# batteryBalancer.net
KiCad netlist of a schematic drawn in EAGLE
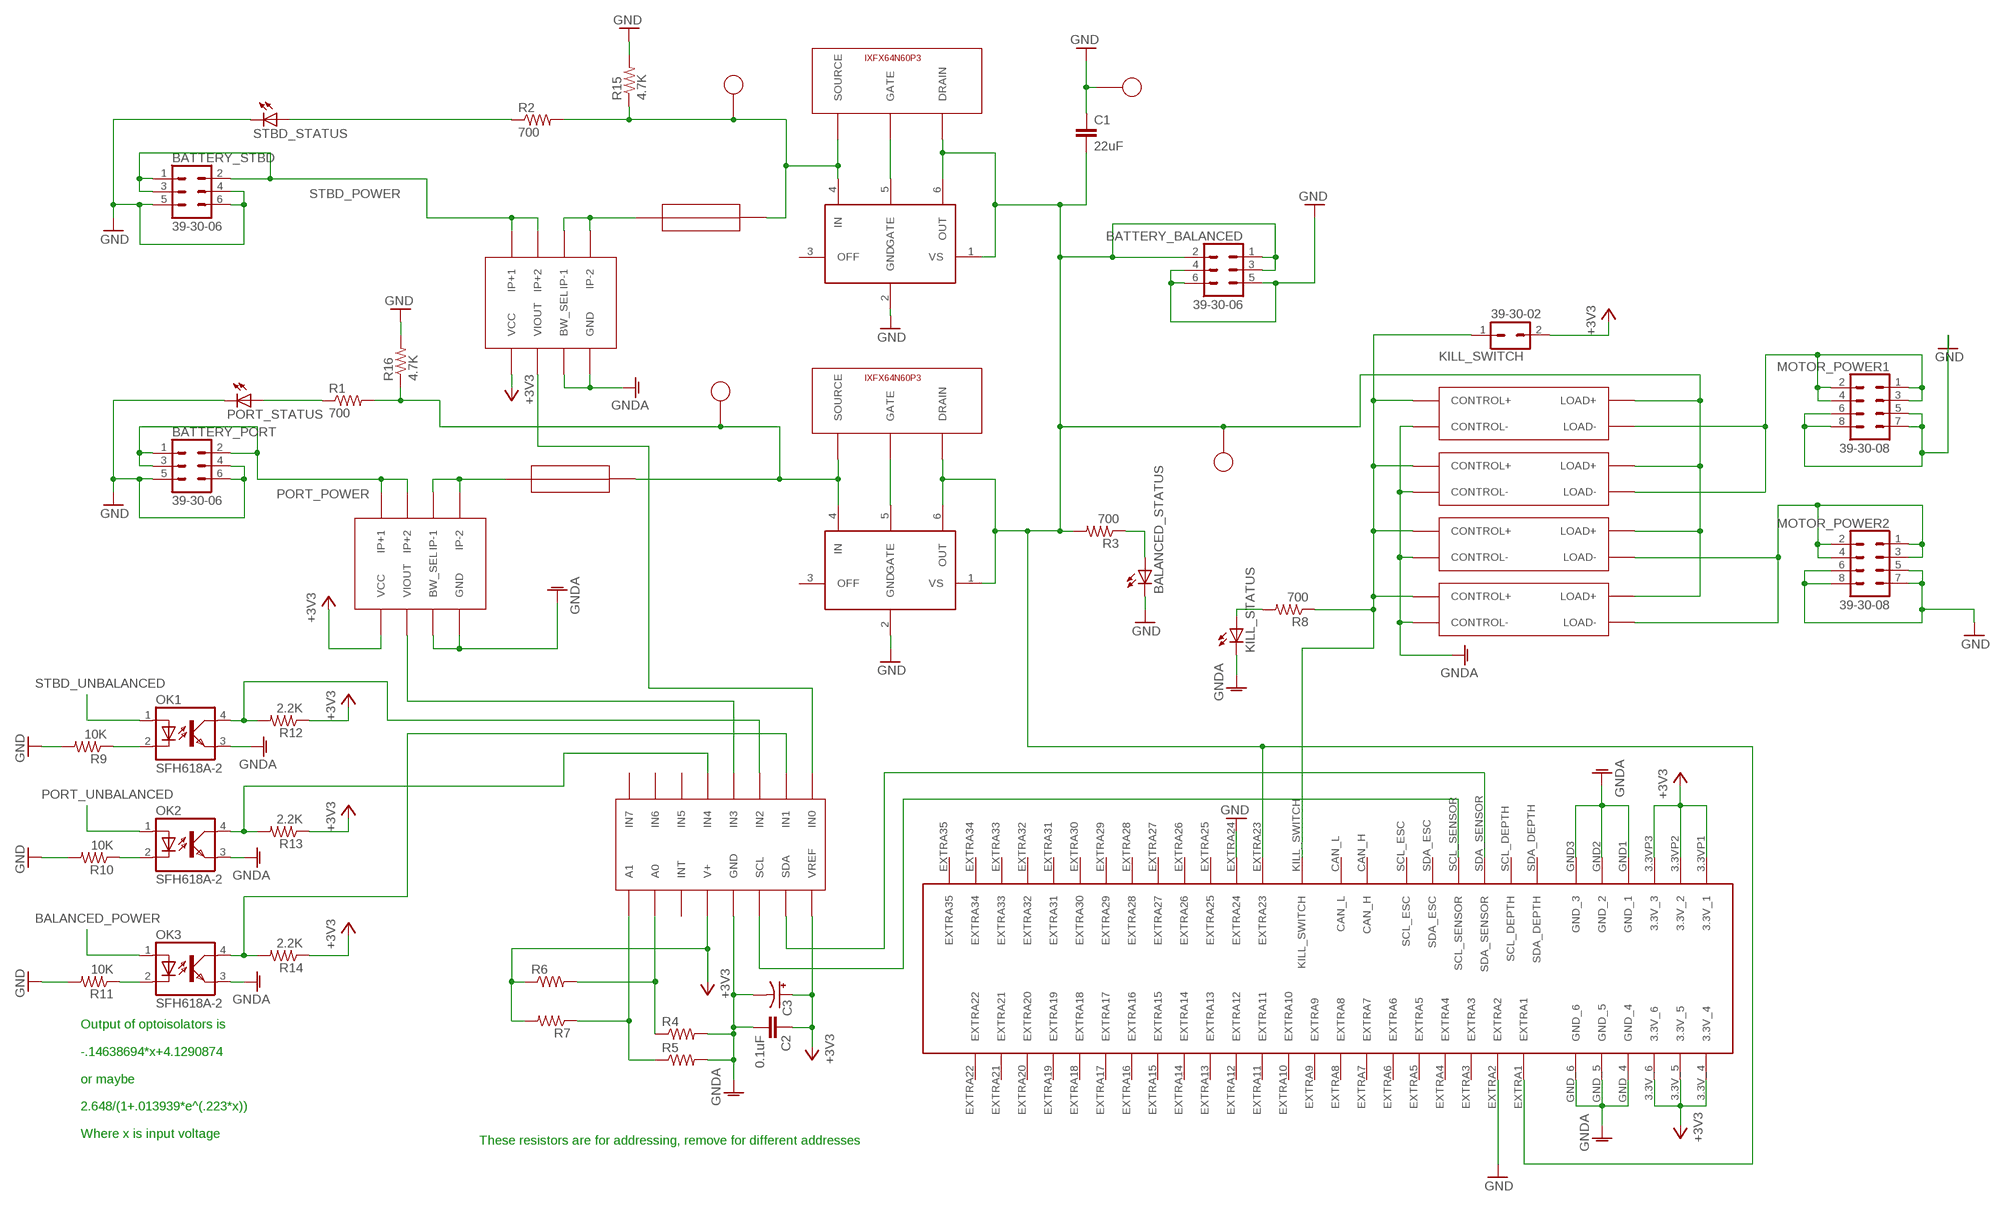
[diagram p0: schematic, sheet 1]

(export (version "E")
  (design (tool "Eeschema 10.0.6"))
  (components
    (comp (ref "ADC")
      (value "ADC128D818")
      (footprint "eagle-import:TSSOP-16")
      (libsource (lib "eagle-import") (part "ADC128D818"))
    )
    (comp (ref "BALANCED_STATUS")
      (value "LTST-S270GKT")
      (footprint "eagle-import:LTST-S270GKT")
      (libsource (lib "eagle-import") (part "LTST-S270GKT"))
    )
    (comp (ref "BATTERY_BALANCED")
      (value "39-30-06")
      (footprint "eagle-import:39-30-_06_")
      (libsource (lib "eagle-import") (part "39-30-?06?"))
    )
    (comp (ref "BATTERY_PORT")
      (value "39-30-06")
      (footprint "eagle-import:39-30-_06_")
      (libsource (lib "eagle-import") (part "39-30-?06?"))
    )
    (comp (ref "BATTERY_STBD")
      (value "39-30-06")
      (footprint "eagle-import:39-30-_06_")
      (libsource (lib "eagle-import") (part "39-30-?06?"))
    )
    (comp (ref "C1")
      (value "22uF")
      (footprint "eagle-import:CAP-PTH-SMALL-KIT")
      (libsource (lib "eagle-import") (part "0.1UF-KIT-EZ-50V-20%"))
    )
    (comp (ref "C2")
      (value "0.1uF")
      (footprint "eagle-import:CAP-PTH-SMALL-KIT")
      (libsource (lib "eagle-import") (part "0.1UF-KIT-EZ-50V-20%"))
    )
    (comp (ref "C3")
      (value "CPOL-USE2-4")
      (footprint "eagle-import:E2-4")
      (libsource (lib "eagle-import") (part "CPOL-USE2-4"))
    )
    (comp (ref "EDGE_CONNECTOR")
      (value "5530843")
      (footprint "eagle-import:5530843-6-BOARDFINGERS")
      (libsource (lib "eagle-import") (part "5530843"))
    )
    (comp (ref "KILL_STATUS")
      (value "LTST-S270GKT")
      (footprint "eagle-import:LTST-S270GKT")
      (libsource (lib "eagle-import") (part "LTST-S270GKT"))
    )
    (comp (ref "KILL_SWITCH")
      (value "39-30-02")
      (footprint "eagle-import:39-30-_02_")
      (libsource (lib "eagle-import") (part "39-30-?02?"))
    )
    (comp (ref "MOTOR_POWER1")
      (value "39-30-08")
      (footprint "eagle-import:39-30-_08_")
      (libsource (lib "eagle-import") (part "39-30-?08?"))
    )
    (comp (ref "MOTOR_POWER2")
      (value "39-30-08")
      (footprint "eagle-import:39-30-_08_")
      (libsource (lib "eagle-import") (part "39-30-?08?"))
    )
    (comp (ref "OK1")
      (value "SFH618A-2")
      (footprint "eagle-import:DIP4")
      (fields (field (name "MF") "VISHAY/TELEFUNKEN"))
      (libsource (lib "eagle-import") (part "SFH618?A-2"))
    )
    (comp (ref "OK2")
      (value "SFH618A-2")
      (footprint "eagle-import:DIP4")
      (fields (field (name "MF") "VISHAY/TELEFUNKEN"))
      (libsource (lib "eagle-import") (part "SFH618?A-2"))
    )
    (comp (ref "OK3")
      (value "SFH618A-2")
      (footprint "eagle-import:DIP4")
      (fields (field (name "MF") "VISHAY/TELEFUNKEN"))
      (libsource (lib "eagle-import") (part "SFH618?A-2"))
    )
    (comp (ref "PORT_CS")
      (value "ACS722")
      (footprint "eagle-import:SOIC-8")
      (libsource (lib "eagle-import") (part "ACS722"))
    )
    (comp (ref "PORT_FC")
      (value "LM5050-1")
      (footprint "eagle-import:SOT23-6")
      (libsource (lib "eagle-import") (part "LM5050-1"))
    )
    (comp (ref "PORT_FET")
      (value "IXFX64N60P3")
      (footprint "eagle-import:IXFX64N60P3")
      (libsource (lib "eagle-import") (part "IXFX64N60P3"))
    )
    (comp (ref "PORT_FUSE")
      (value "01220083Z")
      (footprint "eagle-import:01220083Z")
      (libsource (lib "eagle-import") (part "01220083Z"))
    )
    (comp (ref "PORT_STATUS")
      (value "LTST-S270GKT")
      (footprint "eagle-import:LTST-S270GKT")
      (libsource (lib "eagle-import") (part "LTST-S270GKT"))
    )
    (comp (ref "R1")
      (value "700")
      (footprint "eagle-import:0207_7")
      (libsource (lib "eagle-import") (part "R-US_0207/7"))
    )
    (comp (ref "R2")
      (value "700")
      (footprint "eagle-import:0207_7")
      (libsource (lib "eagle-import") (part "R-US_0207/7"))
    )
    (comp (ref "R3")
      (value "700")
      (footprint "eagle-import:0207_7")
      (libsource (lib "eagle-import") (part "R-US_0207/7"))
    )
    (comp (ref "R4")
      (value "R-US_0204/5")
      (footprint "eagle-import:0204_5")
      (libsource (lib "eagle-import") (part "resistor_348_R-US_0204/5"))
    )
    (comp (ref "R5")
      (value "R-US_0204/5")
      (footprint "eagle-import:0204_5")
      (libsource (lib "eagle-import") (part "resistor_348_R-US_0204/5"))
    )
    (comp (ref "R6")
      (value "R-US_0204/5")
      (footprint "eagle-import:0204_5")
      (libsource (lib "eagle-import") (part "resistor_348_R-US_0204/5"))
    )
    (comp (ref "R7")
      (value "R-US_0204/5")
      (footprint "eagle-import:0204_5")
      (libsource (lib "eagle-import") (part "resistor_348_R-US_0204/5"))
    )
    (comp (ref "R8")
      (value "700")
      (footprint "eagle-import:0207_7")
      (libsource (lib "eagle-import") (part "R-US_0207/7"))
    )
    (comp (ref "R9")
      (value "10K")
      (footprint "eagle-import:0207_7")
      (libsource (lib "eagle-import") (part "R-US_0207/7"))
    )
    (comp (ref "R10")
      (value "10K")
      (footprint "eagle-import:0207_7")
      (libsource (lib "eagle-import") (part "R-US_0207/7"))
    )
    (comp (ref "R11")
      (value "10K")
      (footprint "eagle-import:0207_7")
      (libsource (lib "eagle-import") (part "R-US_0207/7"))
    )
    (comp (ref "R12")
      (value "2.2K")
      (footprint "eagle-import:0207_7")
      (libsource (lib "eagle-import") (part "R-US_0207/7"))
    )
    (comp (ref "R13")
      (value "2.2K")
      (footprint "eagle-import:0207_7")
      (libsource (lib "eagle-import") (part "R-US_0207/7"))
    )
    (comp (ref "R14")
      (value "2.2K")
      (footprint "eagle-import:0207_7")
      (libsource (lib "eagle-import") (part "R-US_0207/7"))
    )
    (comp (ref "R15")
      (value "4.7K")
      (footprint "eagle-import:0207_7")
      (libsource (lib "eagle-import") (part "R-US_0207/7"))
    )
    (comp (ref "R16")
      (value "4.7K")
      (footprint "eagle-import:0207_7")
      (libsource (lib "eagle-import") (part "R-US_0207/7"))
    )
    (comp (ref "RELAY2")
      (value "CMX60D20")
      (footprint "eagle-import:CMX60D20")
      (libsource (lib "eagle-import") (part "CMX60D20"))
    )
    (comp (ref "RELAY3")
      (value "CMX60D20")
      (footprint "eagle-import:CMX60D20")
      (libsource (lib "eagle-import") (part "CMX60D20"))
    )
    (comp (ref "RELAY4")
      (value "CMX60D20")
      (footprint "eagle-import:CMX60D20")
      (libsource (lib "eagle-import") (part "CMX60D20"))
    )
    (comp (ref "RLAY1")
      (value "CMX60D20")
      (footprint "eagle-import:CMX60D20")
      (libsource (lib "eagle-import") (part "CMX60D20"))
    )
    (comp (ref "STBD_CS")
      (value "ACS722")
      (footprint "eagle-import:SOIC-8")
      (libsource (lib "eagle-import") (part "ACS722"))
    )
    (comp (ref "STBD_FC")
      (value "LM5050-1")
      (footprint "eagle-import:SOT23-6")
      (libsource (lib "eagle-import") (part "LM5050-1"))
    )
    (comp (ref "STBD_FET")
      (value "IXFX64N60P3")
      (footprint "eagle-import:IXFX64N60P3")
      (libsource (lib "eagle-import") (part "IXFX64N60P3"))
    )
    (comp (ref "STBD_FUSE")
      (value "01220083Z")
      (footprint "eagle-import:01220083Z")
      (libsource (lib "eagle-import") (part "01220083Z"))
    )
    (comp (ref "STBD_STATUS")
      (value "LTST-S270GKT")
      (footprint "eagle-import:LTST-S270GKT")
      (libsource (lib "eagle-import") (part "LTST-S270GKT"))
    )
    (comp (ref "U$1")
      (value "5010_C")
      (footprint "eagle-import:5010_C")
      (libsource (lib "eagle-import") (part "5010_C"))
    )
    (comp (ref "U$2")
      (value "5010_C")
      (footprint "eagle-import:5010_C")
      (libsource (lib "eagle-import") (part "5010_C"))
    )
    (comp (ref "U$3")
      (value "5010_C")
      (footprint "eagle-import:5010_C")
      (libsource (lib "eagle-import") (part "5010_C"))
    )
    (comp (ref "U$4")
      (value "5010_C")
      (footprint "eagle-import:5010_C")
      (libsource (lib "eagle-import") (part "5010_C"))
    )
  )
  (nets
    (net (code "1") (name "+3V3") (class "Default")
      (node (ref "ADC") (pin "V+") (pinfunction "V+_V+") (pintype "bidirectional"))
      (node (ref "ADC") (pin "VREF") (pinfunction "VREF_VREF") (pintype "bidirectional"))
      (node (ref "C2") (pin "1") (pinfunction "1_1") (pintype "passive"))
      (node (ref "C3") (pin "+") (pinfunction "+_+") (pintype "passive"))
      (node (ref "EDGE_CONNECTOR") (pin "3.3VP1") (pinfunction "3.3V_1_3.3VP1") (pintype "bidirectional"))
      (node (ref "EDGE_CONNECTOR") (pin "3.3VP2") (pinfunction "3.3V_2_3.3VP2") (pintype "bidirectional"))
      (node (ref "EDGE_CONNECTOR") (pin "3.3VP3") (pinfunction "3.3V_3_3.3VP3") (pintype "bidirectional"))
      (node (ref "EDGE_CONNECTOR") (pin "3.3V_4") (pinfunction "3.3V_4_3.3V_4") (pintype "bidirectional"))
      (node (ref "EDGE_CONNECTOR") (pin "3.3V_5") (pinfunction "3.3V_5_3.3V_5") (pintype "bidirectional"))
      (node (ref "EDGE_CONNECTOR") (pin "3.3V_6") (pinfunction "3.3V_6_3.3V_6") (pintype "bidirectional"))
      (node (ref "KILL_SWITCH") (pin "2") (pinfunction "2_2") (pintype "passive"))
      (node (ref "PORT_CS") (pin "VCC") (pinfunction "VCC_VCC") (pintype "bidirectional"))
      (node (ref "R12") (pin "1") (pinfunction "1_1") (pintype "passive"))
      (node (ref "R13") (pin "1") (pinfunction "1_1") (pintype "passive"))
      (node (ref "R14") (pin "1") (pinfunction "1_1") (pintype "passive"))
      (node (ref "R6") (pin "1") (pinfunction "1_1") (pintype "passive"))
      (node (ref "R7") (pin "2") (pinfunction "2_2") (pintype "passive"))
      (node (ref "STBD_CS") (pin "VCC") (pinfunction "VCC_VCC") (pintype "bidirectional"))
    )
    (net (code "2") (name "/BALANCED_POWER") (class "Default")
      (node (ref "BATTERY_BALANCED") (pin "1") (pinfunction "1_1") (pintype "passive"))
      (node (ref "BATTERY_BALANCED") (pin "2") (pinfunction "2_2") (pintype "passive"))
      (node (ref "BATTERY_BALANCED") (pin "3") (pinfunction "3_3") (pintype "passive"))
      (node (ref "C1") (pin "2") (pinfunction "2_2") (pintype "passive"))
      (node (ref "EDGE_CONNECTOR") (pin "EXTRA1") (pinfunction "EXTRA1_EXTRA1") (pintype "bidirectional"))
      (node (ref "EDGE_CONNECTOR") (pin "EXTRA23") (pinfunction "EXTRA23_EXTRA23") (pintype "bidirectional"))
      (node (ref "OK3") (pin "1") (pinfunction "A_1") (pintype "passive"))
      (node (ref "PORT_FC") (pin "1") (pinfunction "VS_1") (pintype "bidirectional"))
      (node (ref "PORT_FC") (pin "6") (pinfunction "OUT_6") (pintype "bidirectional"))
      (node (ref "PORT_FET") (pin "DRAIN") (pinfunction "DRAIN_DRAIN") (pintype "bidirectional"))
      (node (ref "R3") (pin "2") (pinfunction "2_2") (pintype "passive"))
      (node (ref "RELAY2") (pin "LOAD+") (pinfunction "LOAD+_LOAD+") (pintype "bidirectional"))
      (node (ref "RELAY3") (pin "LOAD+") (pinfunction "LOAD+_LOAD+") (pintype "bidirectional"))
      (node (ref "RELAY4") (pin "LOAD+") (pinfunction "LOAD+_LOAD+") (pintype "bidirectional"))
      (node (ref "RLAY1") (pin "LOAD+") (pinfunction "LOAD+_LOAD+") (pintype "bidirectional"))
      (node (ref "STBD_FC") (pin "1") (pinfunction "VS_1") (pintype "bidirectional"))
      (node (ref "STBD_FC") (pin "6") (pinfunction "OUT_6") (pintype "bidirectional"))
      (node (ref "STBD_FET") (pin "DRAIN") (pinfunction "DRAIN_DRAIN") (pintype "bidirectional"))
      (node (ref "U$3") (pin "P$1") (pinfunction "P$1_P$1") (pintype "bidirectional"))
    )
    (net (code "3") (name "/PORT_POWER") (class "Default")
      (node (ref "BATTERY_PORT") (pin "1") (pinfunction "1_1") (pintype "passive"))
      (node (ref "BATTERY_PORT") (pin "2") (pinfunction "2_2") (pintype "passive"))
      (node (ref "BATTERY_PORT") (pin "3") (pinfunction "3_3") (pintype "passive"))
      (node (ref "PORT_CS") (pin "IP+1") (pinfunction "IP+1_IP+1") (pintype "bidirectional"))
      (node (ref "PORT_CS") (pin "IP+2") (pinfunction "IP+2_IP+2") (pintype "bidirectional"))
    )
    (net (code "4") (name "/PORT_UNBALANCED") (class "Default")
      (node (ref "OK2") (pin "1") (pinfunction "A_1") (pintype "passive"))
      (node (ref "PORT_FC") (pin "4") (pinfunction "IN_4") (pintype "bidirectional"))
      (node (ref "PORT_FET") (pin "SOURCE") (pinfunction "SOURCE_SOURCE") (pintype "bidirectional"))
      (node (ref "PORT_FUSE") (pin "P$3") (pinfunction "P$2_P$3") (pintype "bidirectional"))
      (node (ref "PORT_FUSE") (pin "P$4") (pinfunction "P$2_P$4") (pintype "bidirectional"))
      (node (ref "R1") (pin "2") (pinfunction "2_2") (pintype "passive"))
      (node (ref "R16") (pin "1") (pinfunction "1_1") (pintype "passive"))
      (node (ref "U$2") (pin "P$1") (pinfunction "P$1_P$1") (pintype "bidirectional"))
    )
    (net (code "5") (name "/STBD_POWER") (class "Default")
      (node (ref "BATTERY_STBD") (pin "1") (pinfunction "1_1") (pintype "passive"))
      (node (ref "BATTERY_STBD") (pin "2") (pinfunction "2_2") (pintype "passive"))
      (node (ref "BATTERY_STBD") (pin "3") (pinfunction "3_3") (pintype "passive"))
      (node (ref "STBD_CS") (pin "IP+1") (pinfunction "IP+1_IP+1") (pintype "bidirectional"))
      (node (ref "STBD_CS") (pin "IP+2") (pinfunction "IP+2_IP+2") (pintype "bidirectional"))
    )
    (net (code "6") (name "/STBD_UNBALANCED") (class "Default")
      (node (ref "OK1") (pin "1") (pinfunction "A_1") (pintype "passive"))
      (node (ref "R15") (pin "1") (pinfunction "1_1") (pintype "passive"))
      (node (ref "R2") (pin "2") (pinfunction "2_2") (pintype "passive"))
      (node (ref "STBD_FC") (pin "4") (pinfunction "IN_4") (pintype "bidirectional"))
      (node (ref "STBD_FET") (pin "SOURCE") (pinfunction "SOURCE_SOURCE") (pintype "bidirectional"))
      (node (ref "STBD_FUSE") (pin "P$3") (pinfunction "P$2_P$3") (pintype "bidirectional"))
      (node (ref "STBD_FUSE") (pin "P$4") (pinfunction "P$2_P$4") (pintype "bidirectional"))
      (node (ref "U$1") (pin "P$1") (pinfunction "P$1_P$1") (pintype "bidirectional"))
    )
    (net (code "7") (name "GND") (class "Default")
      (node (ref "BALANCED_STATUS") (pin "CATHODE") (pinfunction "C_CATHODE") (pintype "passive"))
      (node (ref "BATTERY_BALANCED") (pin "4") (pinfunction "4_4") (pintype "passive"))
      (node (ref "BATTERY_BALANCED") (pin "5") (pinfunction "5_5") (pintype "passive"))
      (node (ref "BATTERY_BALANCED") (pin "6") (pinfunction "6_6") (pintype "passive"))
      (node (ref "BATTERY_PORT") (pin "4") (pinfunction "4_4") (pintype "passive"))
      (node (ref "BATTERY_PORT") (pin "5") (pinfunction "5_5") (pintype "passive"))
      (node (ref "BATTERY_PORT") (pin "6") (pinfunction "6_6") (pintype "passive"))
      (node (ref "BATTERY_STBD") (pin "4") (pinfunction "4_4") (pintype "passive"))
      (node (ref "BATTERY_STBD") (pin "5") (pinfunction "5_5") (pintype "passive"))
      (node (ref "BATTERY_STBD") (pin "6") (pinfunction "6_6") (pintype "passive"))
      (node (ref "C1") (pin "1") (pinfunction "1_1") (pintype "passive"))
      (node (ref "EDGE_CONNECTOR") (pin "EXTRA2") (pinfunction "EXTRA2_EXTRA2") (pintype "bidirectional"))
      (node (ref "EDGE_CONNECTOR") (pin "EXTRA24") (pinfunction "EXTRA24_EXTRA24") (pintype "bidirectional"))
      (node (ref "MOTOR_POWER1") (pin "5") (pinfunction "5_5") (pintype "passive"))
      (node (ref "MOTOR_POWER1") (pin "6") (pinfunction "6_6") (pintype "passive"))
      (node (ref "MOTOR_POWER1") (pin "7") (pinfunction "7_7") (pintype "passive"))
      (node (ref "MOTOR_POWER1") (pin "8") (pinfunction "8_8") (pintype "passive"))
      (node (ref "MOTOR_POWER2") (pin "5") (pinfunction "5_5") (pintype "passive"))
      (node (ref "MOTOR_POWER2") (pin "6") (pinfunction "6_6") (pintype "passive"))
      (node (ref "MOTOR_POWER2") (pin "7") (pinfunction "7_7") (pintype "passive"))
      (node (ref "MOTOR_POWER2") (pin "8") (pinfunction "8_8") (pintype "passive"))
      (node (ref "PORT_FC") (pin "2") (pinfunction "GND_2") (pintype "bidirectional"))
      (node (ref "PORT_STATUS") (pin "CATHODE") (pinfunction "C_CATHODE") (pintype "passive"))
      (node (ref "R10") (pin "2") (pinfunction "2_2") (pintype "passive"))
      (node (ref "R11") (pin "2") (pinfunction "2_2") (pintype "passive"))
      (node (ref "R15") (pin "2") (pinfunction "2_2") (pintype "passive"))
      (node (ref "R16") (pin "2") (pinfunction "2_2") (pintype "passive"))
      (node (ref "R9") (pin "2") (pinfunction "2_2") (pintype "passive"))
      (node (ref "STBD_FC") (pin "2") (pinfunction "GND_2") (pintype "bidirectional"))
      (node (ref "STBD_STATUS") (pin "CATHODE") (pinfunction "C_CATHODE") (pintype "passive"))
      (node (ref "U$4") (pin "P$1") (pinfunction "P$1_P$1") (pintype "bidirectional"))
    )
    (net (code "8") (name "GNDA") (class "Default")
      (node (ref "ADC") (pin "GND") (pinfunction "GND_GND") (pintype "bidirectional"))
      (node (ref "C2") (pin "2") (pinfunction "2_2") (pintype "passive"))
      (node (ref "C3") (pin "-") (pinfunction "-_-") (pintype "passive"))
      (node (ref "EDGE_CONNECTOR") (pin "GND1") (pinfunction "GND_1_GND1") (pintype "bidirectional"))
      (node (ref "EDGE_CONNECTOR") (pin "GND2") (pinfunction "GND_2_GND2") (pintype "bidirectional"))
      (node (ref "EDGE_CONNECTOR") (pin "GND3") (pinfunction "GND_3_GND3") (pintype "bidirectional"))
      (node (ref "EDGE_CONNECTOR") (pin "GND_4") (pinfunction "GND_4_GND_4") (pintype "bidirectional"))
      (node (ref "EDGE_CONNECTOR") (pin "GND_5") (pinfunction "GND_5_GND_5") (pintype "bidirectional"))
      (node (ref "EDGE_CONNECTOR") (pin "GND_6") (pinfunction "GND_6_GND_6") (pintype "bidirectional"))
      (node (ref "KILL_STATUS") (pin "CATHODE") (pinfunction "C_CATHODE") (pintype "passive"))
      (node (ref "OK1") (pin "3") (pinfunction "EMIT_3") (pintype "passive"))
      (node (ref "OK2") (pin "3") (pinfunction "EMIT_3") (pintype "passive"))
      (node (ref "OK3") (pin "3") (pinfunction "EMIT_3") (pintype "passive"))
      (node (ref "PORT_CS") (pin "BW_SEL") (pinfunction "BW_SEL_BW_SEL") (pintype "bidirectional"))
      (node (ref "PORT_CS") (pin "GND") (pinfunction "GND_GND") (pintype "bidirectional"))
      (node (ref "R4") (pin "2") (pinfunction "2_2") (pintype "passive"))
      (node (ref "R5") (pin "2") (pinfunction "2_2") (pintype "passive"))
      (node (ref "RELAY2") (pin "CONTROL-") (pinfunction "CONTROL-_CONTROL-") (pintype "bidirectional"))
      (node (ref "RELAY3") (pin "CONTROL-") (pinfunction "CONTROL-_CONTROL-") (pintype "bidirectional"))
      (node (ref "RELAY4") (pin "CONTROL-") (pinfunction "CONTROL-_CONTROL-") (pintype "bidirectional"))
      (node (ref "RLAY1") (pin "CONTROL-") (pinfunction "CONTROL-_CONTROL-") (pintype "bidirectional"))
      (node (ref "STBD_CS") (pin "BW_SEL") (pinfunction "BW_SEL_BW_SEL") (pintype "bidirectional"))
      (node (ref "STBD_CS") (pin "GND") (pinfunction "GND_GND") (pintype "bidirectional"))
    )
    (net (code "9") (name "Net-(ADC-PadA0)") (class "Default")
      (node (ref "ADC") (pin "A0") (pinfunction "A0_A0") (pintype "bidirectional"))
      (node (ref "R4") (pin "1") (pinfunction "1_1") (pintype "passive"))
      (node (ref "R6") (pin "2") (pinfunction "2_2") (pintype "passive"))
    )
    (net (code "10") (name "Net-(ADC-PadA1)") (class "Default")
      (node (ref "ADC") (pin "A1") (pinfunction "A1_A1") (pintype "bidirectional"))
      (node (ref "R5") (pin "1") (pinfunction "1_1") (pintype "passive"))
      (node (ref "R7") (pin "1") (pinfunction "1_1") (pintype "passive"))
    )
    (net (code "11") (name "Net-(ADC-PadIN0)") (class "Default")
      (node (ref "ADC") (pin "IN0") (pinfunction "IN0_IN0") (pintype "bidirectional"))
      (node (ref "STBD_CS") (pin "VIOUT") (pinfunction "VIOUT_VIOUT") (pintype "bidirectional"))
    )
    (net (code "12") (name "Net-(ADC-PadIN3)") (class "Default")
      (node (ref "ADC") (pin "IN3") (pinfunction "IN3_IN3") (pintype "bidirectional"))
      (node (ref "PORT_CS") (pin "VIOUT") (pinfunction "VIOUT_VIOUT") (pintype "bidirectional"))
    )
    (net (code "13") (name "Net-(ADC-PadSCL)") (class "Default")
      (node (ref "ADC") (pin "SCL") (pinfunction "SCL_SCL") (pintype "bidirectional"))
      (node (ref "EDGE_CONNECTOR") (pin "SCL_SENSOR") (pinfunction "SCL_SENSOR_SCL_SENSOR") (pintype "bidirectional"))
    )
    (net (code "14") (name "Net-(ADC-PadSDA)") (class "Default")
      (node (ref "ADC") (pin "SDA") (pinfunction "SDA_SDA") (pintype "bidirectional"))
      (node (ref "EDGE_CONNECTOR") (pin "SDA_SENSOR") (pinfunction "SDA_SENSOR_SDA_SENSOR") (pintype "bidirectional"))
    )
    (net (code "15") (name "Net-(BALANCED_STATUS-A)") (class "Default")
      (node (ref "BALANCED_STATUS") (pin "ANODE") (pinfunction "A_ANODE") (pintype "passive"))
      (node (ref "R3") (pin "1") (pinfunction "1_1") (pintype "passive"))
    )
    (net (code "16") (name "Net-(EDGE_CONNECTOR-PadKILL_SWITCH)") (class "Default")
      (node (ref "EDGE_CONNECTOR") (pin "KILL_SWITCH") (pinfunction "KILL_SWITCH_KILL_SWITCH") (pintype "bidirectional"))
      (node (ref "KILL_SWITCH") (pin "1") (pinfunction "1_1") (pintype "passive"))
      (node (ref "R8") (pin "1") (pinfunction "1_1") (pintype "passive"))
      (node (ref "RELAY2") (pin "CONTROL+") (pinfunction "CONTROL+_CONTROL+") (pintype "bidirectional"))
      (node (ref "RELAY3") (pin "CONTROL+") (pinfunction "CONTROL+_CONTROL+") (pintype "bidirectional"))
      (node (ref "RELAY4") (pin "CONTROL+") (pinfunction "CONTROL+_CONTROL+") (pintype "bidirectional"))
      (node (ref "RLAY1") (pin "CONTROL+") (pinfunction "CONTROL+_CONTROL+") (pintype "bidirectional"))
    )
    (net (code "17") (name "Net-(KILL_STATUS-A)") (class "Default")
      (node (ref "KILL_STATUS") (pin "ANODE") (pinfunction "A_ANODE") (pintype "passive"))
      (node (ref "R8") (pin "2") (pinfunction "2_2") (pintype "passive"))
    )
    (net (code "18") (name "Net-(MOTOR_POWER1-Pad1)") (class "Default")
      (node (ref "MOTOR_POWER1") (pin "1") (pinfunction "1_1") (pintype "passive"))
      (node (ref "MOTOR_POWER1") (pin "2") (pinfunction "2_2") (pintype "passive"))
      (node (ref "MOTOR_POWER1") (pin "3") (pinfunction "3_3") (pintype "passive"))
      (node (ref "MOTOR_POWER1") (pin "4") (pinfunction "4_4") (pintype "passive"))
      (node (ref "RELAY2") (pin "LOAD-") (pinfunction "LOAD-_LOAD-") (pintype "bidirectional"))
      (node (ref "RLAY1") (pin "LOAD-") (pinfunction "LOAD-_LOAD-") (pintype "bidirectional"))
    )
    (net (code "19") (name "Net-(MOTOR_POWER2-Pad1)") (class "Default")
      (node (ref "MOTOR_POWER2") (pin "1") (pinfunction "1_1") (pintype "passive"))
      (node (ref "MOTOR_POWER2") (pin "2") (pinfunction "2_2") (pintype "passive"))
      (node (ref "MOTOR_POWER2") (pin "3") (pinfunction "3_3") (pintype "passive"))
      (node (ref "MOTOR_POWER2") (pin "4") (pinfunction "4_4") (pintype "passive"))
      (node (ref "RELAY3") (pin "LOAD-") (pinfunction "LOAD-_LOAD-") (pintype "bidirectional"))
      (node (ref "RELAY4") (pin "LOAD-") (pinfunction "LOAD-_LOAD-") (pintype "bidirectional"))
    )
    (net (code "20") (name "Net-(OK1-C)") (class "Default")
      (node (ref "OK1") (pin "2") (pinfunction "C_2") (pintype "passive"))
      (node (ref "R9") (pin "1") (pinfunction "1_1") (pintype "passive"))
    )
    (net (code "21") (name "Net-(OK1-COL)") (class "Default")
      (node (ref "ADC") (pin "IN2") (pinfunction "IN2_IN2") (pintype "bidirectional"))
      (node (ref "OK1") (pin "4") (pinfunction "COL_4") (pintype "passive"))
      (node (ref "R12") (pin "2") (pinfunction "2_2") (pintype "passive"))
    )
    (net (code "22") (name "Net-(OK2-C)") (class "Default")
      (node (ref "OK2") (pin "2") (pinfunction "C_2") (pintype "passive"))
      (node (ref "R10") (pin "1") (pinfunction "1_1") (pintype "passive"))
    )
    (net (code "23") (name "Net-(OK2-COL)") (class "Default")
      (node (ref "ADC") (pin "IN4") (pinfunction "IN4_IN4") (pintype "bidirectional"))
      (node (ref "OK2") (pin "4") (pinfunction "COL_4") (pintype "passive"))
      (node (ref "R13") (pin "2") (pinfunction "2_2") (pintype "passive"))
    )
    (net (code "24") (name "Net-(OK3-C)") (class "Default")
      (node (ref "OK3") (pin "2") (pinfunction "C_2") (pintype "passive"))
      (node (ref "R11") (pin "1") (pinfunction "1_1") (pintype "passive"))
    )
    (net (code "25") (name "Net-(OK3-COL)") (class "Default")
      (node (ref "ADC") (pin "IN1") (pinfunction "IN1_IN1") (pintype "bidirectional"))
      (node (ref "OK3") (pin "4") (pinfunction "COL_4") (pintype "passive"))
      (node (ref "R14") (pin "2") (pinfunction "2_2") (pintype "passive"))
    )
    (net (code "26") (name "Net-(PORT_CS-PadIP-1)") (class "Default")
      (node (ref "PORT_CS") (pin "IP-1") (pinfunction "IP-1_IP-1") (pintype "bidirectional"))
      (node (ref "PORT_CS") (pin "IP-2") (pinfunction "IP-2_IP-2") (pintype "bidirectional"))
      (node (ref "PORT_FUSE") (pin "P$1") (pinfunction "P$1_P$1") (pintype "bidirectional"))
      (node (ref "PORT_FUSE") (pin "P$2") (pinfunction "P$1_P$2") (pintype "bidirectional"))
    )
    (net (code "27") (name "Net-(PORT_FC-GATE)") (class "Default")
      (node (ref "PORT_FC") (pin "5") (pinfunction "GATE_5") (pintype "bidirectional"))
      (node (ref "PORT_FET") (pin "GATE") (pinfunction "GATE_GATE") (pintype "bidirectional"))
    )
    (net (code "28") (name "Net-(PORT_STATUS-A)") (class "Default")
      (node (ref "PORT_STATUS") (pin "ANODE") (pinfunction "A_ANODE") (pintype "passive"))
      (node (ref "R1") (pin "1") (pinfunction "1_1") (pintype "passive"))
    )
    (net (code "29") (name "Net-(STBD_CS-PadIP-1)") (class "Default")
      (node (ref "STBD_CS") (pin "IP-1") (pinfunction "IP-1_IP-1") (pintype "bidirectional"))
      (node (ref "STBD_CS") (pin "IP-2") (pinfunction "IP-2_IP-2") (pintype "bidirectional"))
      (node (ref "STBD_FUSE") (pin "P$1") (pinfunction "P$1_P$1") (pintype "bidirectional"))
      (node (ref "STBD_FUSE") (pin "P$2") (pinfunction "P$1_P$2") (pintype "bidirectional"))
    )
    (net (code "30") (name "Net-(STBD_FC-GATE)") (class "Default")
      (node (ref "STBD_FC") (pin "5") (pinfunction "GATE_5") (pintype "bidirectional"))
      (node (ref "STBD_FET") (pin "GATE") (pinfunction "GATE_GATE") (pintype "bidirectional"))
    )
    (net (code "31") (name "Net-(STBD_STATUS-A)") (class "Default")
      (node (ref "R2") (pin "1") (pinfunction "1_1") (pintype "passive"))
      (node (ref "STBD_STATUS") (pin "ANODE") (pinfunction "A_ANODE") (pintype "passive"))
    )
    (net (code "32") (name "unconnected-(ADC-PadIN5)") (class "Default")
      (node (ref "ADC") (pin "IN5") (pinfunction "IN5_IN5") (pintype "bidirectional"))
    )
    (net (code "33") (name "unconnected-(ADC-PadIN6)") (class "Default")
      (node (ref "ADC") (pin "IN6") (pinfunction "IN6_IN6") (pintype "bidirectional"))
    )
    (net (code "34") (name "unconnected-(ADC-PadIN7)") (class "Default")
      (node (ref "ADC") (pin "IN7") (pinfunction "IN7_IN7") (pintype "bidirectional"))
    )
    (net (code "35") (name "unconnected-(ADC-PadINT)") (class "Default")
      (node (ref "ADC") (pin "INT") (pinfunction "INT_INT") (pintype "bidirectional"))
    )
    (net (code "36") (name "unconnected-(EDGE_CONNECTOR-PadCAN_H)") (class "Default")
      (node (ref "EDGE_CONNECTOR") (pin "CAN_H") (pinfunction "CAN_H_CAN_H") (pintype "bidirectional"))
    )
    (net (code "37") (name "unconnected-(EDGE_CONNECTOR-PadCAN_L)") (class "Default")
      (node (ref "EDGE_CONNECTOR") (pin "CAN_L") (pinfunction "CAN_L_CAN_L") (pintype "bidirectional"))
    )
    (net (code "38") (name "unconnected-(EDGE_CONNECTOR-PadEXTRA3)") (class "Default")
      (node (ref "EDGE_CONNECTOR") (pin "EXTRA3") (pinfunction "EXTRA3_EXTRA3") (pintype "bidirectional"))
    )
    (net (code "39") (name "unconnected-(EDGE_CONNECTOR-PadEXTRA4)") (class "Default")
      (node (ref "EDGE_CONNECTOR") (pin "EXTRA4") (pinfunction "EXTRA4_EXTRA4") (pintype "bidirectional"))
    )
    (net (code "40") (name "unconnected-(EDGE_CONNECTOR-PadEXTRA5)") (class "Default")
      (node (ref "EDGE_CONNECTOR") (pin "EXTRA5") (pinfunction "EXTRA5_EXTRA5") (pintype "bidirectional"))
    )
    (net (code "41") (name "unconnected-(EDGE_CONNECTOR-PadEXTRA6)") (class "Default")
      (node (ref "EDGE_CONNECTOR") (pin "EXTRA6") (pinfunction "EXTRA6_EXTRA6") (pintype "bidirectional"))
    )
    (net (code "42") (name "unconnected-(EDGE_CONNECTOR-PadEXTRA7)") (class "Default")
      (node (ref "EDGE_CONNECTOR") (pin "EXTRA7") (pinfunction "EXTRA7_EXTRA7") (pintype "bidirectional"))
    )
    (net (code "43") (name "unconnected-(EDGE_CONNECTOR-PadEXTRA8)") (class "Default")
      (node (ref "EDGE_CONNECTOR") (pin "EXTRA8") (pinfunction "EXTRA8_EXTRA8") (pintype "bidirectional"))
    )
    (net (code "44") (name "unconnected-(EDGE_CONNECTOR-PadEXTRA9)") (class "Default")
      (node (ref "EDGE_CONNECTOR") (pin "EXTRA9") (pinfunction "EXTRA9_EXTRA9") (pintype "bidirectional"))
    )
    (net (code "45") (name "unconnected-(EDGE_CONNECTOR-PadEXTRA10)") (class "Default")
      (node (ref "EDGE_CONNECTOR") (pin "EXTRA10") (pinfunction "EXTRA10_EXTRA10") (pintype "bidirectional"))
    )
    (net (code "46") (name "unconnected-(EDGE_CONNECTOR-PadEXTRA11)") (class "Default")
      (node (ref "EDGE_CONNECTOR") (pin "EXTRA11") (pinfunction "EXTRA11_EXTRA11") (pintype "bidirectional"))
    )
    (net (code "47") (name "unconnected-(EDGE_CONNECTOR-PadEXTRA12)") (class "Default")
      (node (ref "EDGE_CONNECTOR") (pin "EXTRA12") (pinfunction "EXTRA12_EXTRA12") (pintype "bidirectional"))
    )
    (net (code "48") (name "unconnected-(EDGE_CONNECTOR-PadEXTRA13)") (class "Default")
      (node (ref "EDGE_CONNECTOR") (pin "EXTRA13") (pinfunction "EXTRA13_EXTRA13") (pintype "bidirectional"))
    )
    (net (code "49") (name "unconnected-(EDGE_CONNECTOR-PadEXTRA14)") (class "Default")
      (node (ref "EDGE_CONNECTOR") (pin "EXTRA14") (pinfunction "EXTRA14_EXTRA14") (pintype "bidirectional"))
    )
    (net (code "50") (name "unconnected-(EDGE_CONNECTOR-PadEXTRA15)") (class "Default")
      (node (ref "EDGE_CONNECTOR") (pin "EXTRA15") (pinfunction "EXTRA15_EXTRA15") (pintype "bidirectional"))
    )
    (net (code "51") (name "unconnected-(EDGE_CONNECTOR-PadEXTRA16)") (class "Default")
      (node (ref "EDGE_CONNECTOR") (pin "EXTRA16") (pinfunction "EXTRA16_EXTRA16") (pintype "bidirectional"))
    )
    (net (code "52") (name "unconnected-(EDGE_CONNECTOR-PadEXTRA17)") (class "Default")
      (node (ref "EDGE_CONNECTOR") (pin "EXTRA17") (pinfunction "EXTRA17_EXTRA17") (pintype "bidirectional"))
    )
    (net (code "53") (name "unconnected-(EDGE_CONNECTOR-PadEXTRA18)") (class "Default")
      (node (ref "EDGE_CONNECTOR") (pin "EXTRA18") (pinfunction "EXTRA18_EXTRA18") (pintype "bidirectional"))
    )
    (net (code "54") (name "unconnected-(EDGE_CONNECTOR-PadEXTRA19)") (class "Default")
      (node (ref "EDGE_CONNECTOR") (pin "EXTRA19") (pinfunction "EXTRA19_EXTRA19") (pintype "bidirectional"))
    )
    (net (code "55") (name "unconnected-(EDGE_CONNECTOR-PadEXTRA20)") (class "Default")
      (node (ref "EDGE_CONNECTOR") (pin "EXTRA20") (pinfunction "EXTRA20_EXTRA20") (pintype "bidirectional"))
    )
    (net (code "56") (name "unconnected-(EDGE_CONNECTOR-PadEXTRA21)") (class "Default")
      (node (ref "EDGE_CONNECTOR") (pin "EXTRA21") (pinfunction "EXTRA21_EXTRA21") (pintype "bidirectional"))
    )
    (net (code "57") (name "unconnected-(EDGE_CONNECTOR-PadEXTRA22)") (class "Default")
      (node (ref "EDGE_CONNECTOR") (pin "EXTRA22") (pinfunction "EXTRA22_EXTRA22") (pintype "bidirectional"))
    )
    (net (code "58") (name "unconnected-(EDGE_CONNECTOR-PadEXTRA25)") (class "Default")
      (node (ref "EDGE_CONNECTOR") (pin "EXTRA25") (pinfunction "EXTRA25_EXTRA25") (pintype "bidirectional"))
    )
    (net (code "59") (name "unconnected-(EDGE_CONNECTOR-PadEXTRA26)") (class "Default")
      (node (ref "EDGE_CONNECTOR") (pin "EXTRA26") (pinfunction "EXTRA26_EXTRA26") (pintype "bidirectional"))
    )
    (net (code "60") (name "unconnected-(EDGE_CONNECTOR-PadEXTRA27)") (class "Default")
      (node (ref "EDGE_CONNECTOR") (pin "EXTRA27") (pinfunction "EXTRA27_EXTRA27") (pintype "bidirectional"))
    )
    (net (code "61") (name "unconnected-(EDGE_CONNECTOR-PadEXTRA28)") (class "Default")
      (node (ref "EDGE_CONNECTOR") (pin "EXTRA28") (pinfunction "EXTRA28_EXTRA28") (pintype "bidirectional"))
    )
    (net (code "62") (name "unconnected-(EDGE_CONNECTOR-PadEXTRA29)") (class "Default")
      (node (ref "EDGE_CONNECTOR") (pin "EXTRA29") (pinfunction "EXTRA29_EXTRA29") (pintype "bidirectional"))
    )
    (net (code "63") (name "unconnected-(EDGE_CONNECTOR-PadEXTRA30)") (class "Default")
      (node (ref "EDGE_CONNECTOR") (pin "EXTRA30") (pinfunction "EXTRA30_EXTRA30") (pintype "bidirectional"))
    )
    (net (code "64") (name "unconnected-(EDGE_CONNECTOR-PadEXTRA31)") (class "Default")
      (node (ref "EDGE_CONNECTOR") (pin "EXTRA31") (pinfunction "EXTRA31_EXTRA31") (pintype "bidirectional"))
    )
    (net (code "65") (name "unconnected-(EDGE_CONNECTOR-PadEXTRA32)") (class "Default")
      (node (ref "EDGE_CONNECTOR") (pin "EXTRA32") (pinfunction "EXTRA32_EXTRA32") (pintype "bidirectional"))
    )
    (net (code "66") (name "unconnected-(EDGE_CONNECTOR-PadEXTRA33)") (class "Default")
      (node (ref "EDGE_CONNECTOR") (pin "EXTRA33") (pinfunction "EXTRA33_EXTRA33") (pintype "bidirectional"))
    )
    (net (code "67") (name "unconnected-(EDGE_CONNECTOR-PadEXTRA34)") (class "Default")
      (node (ref "EDGE_CONNECTOR") (pin "EXTRA34") (pinfunction "EXTRA34_EXTRA34") (pintype "bidirectional"))
    )
    (net (code "68") (name "unconnected-(EDGE_CONNECTOR-PadEXTRA35)") (class "Default")
      (node (ref "EDGE_CONNECTOR") (pin "EXTRA35") (pinfunction "EXTRA35_EXTRA35") (pintype "bidirectional"))
    )
    (net (code "69") (name "unconnected-(EDGE_CONNECTOR-PadSCL_DEPTH)") (class "Default")
      (node (ref "EDGE_CONNECTOR") (pin "SCL_DEPTH") (pinfunction "SCL_DEPTH_SCL_DEPTH") (pintype "bidirectional"))
    )
    (net (code "70") (name "unconnected-(EDGE_CONNECTOR-PadSCL_ESC)") (class "Default")
      (node (ref "EDGE_CONNECTOR") (pin "SCL_ESC") (pinfunction "SCL_ESC_SCL_ESC") (pintype "bidirectional"))
    )
    (net (code "71") (name "unconnected-(EDGE_CONNECTOR-PadSDA_DEPTH)") (class "Default")
      (node (ref "EDGE_CONNECTOR") (pin "SDA_DEPTH") (pinfunction "SDA_DEPTH_SDA_DEPTH") (pintype "bidirectional"))
    )
    (net (code "72") (name "unconnected-(EDGE_CONNECTOR-PadSDA_ESC)") (class "Default")
      (node (ref "EDGE_CONNECTOR") (pin "SDA_ESC") (pinfunction "SDA_ESC_SDA_ESC") (pintype "bidirectional"))
    )
    (net (code "73") (name "unconnected-(PORT_FC-OFF-Pad3)") (class "Default")
      (node (ref "PORT_FC") (pin "3") (pinfunction "OFF_3") (pintype "bidirectional"))
    )
    (net (code "74") (name "unconnected-(STBD_FC-OFF-Pad3)") (class "Default")
      (node (ref "STBD_FC") (pin "3") (pinfunction "OFF_3") (pintype "bidirectional"))
    )
  )
)
